# adc.net
KiCad netlist of a schematic drawn in EAGLE
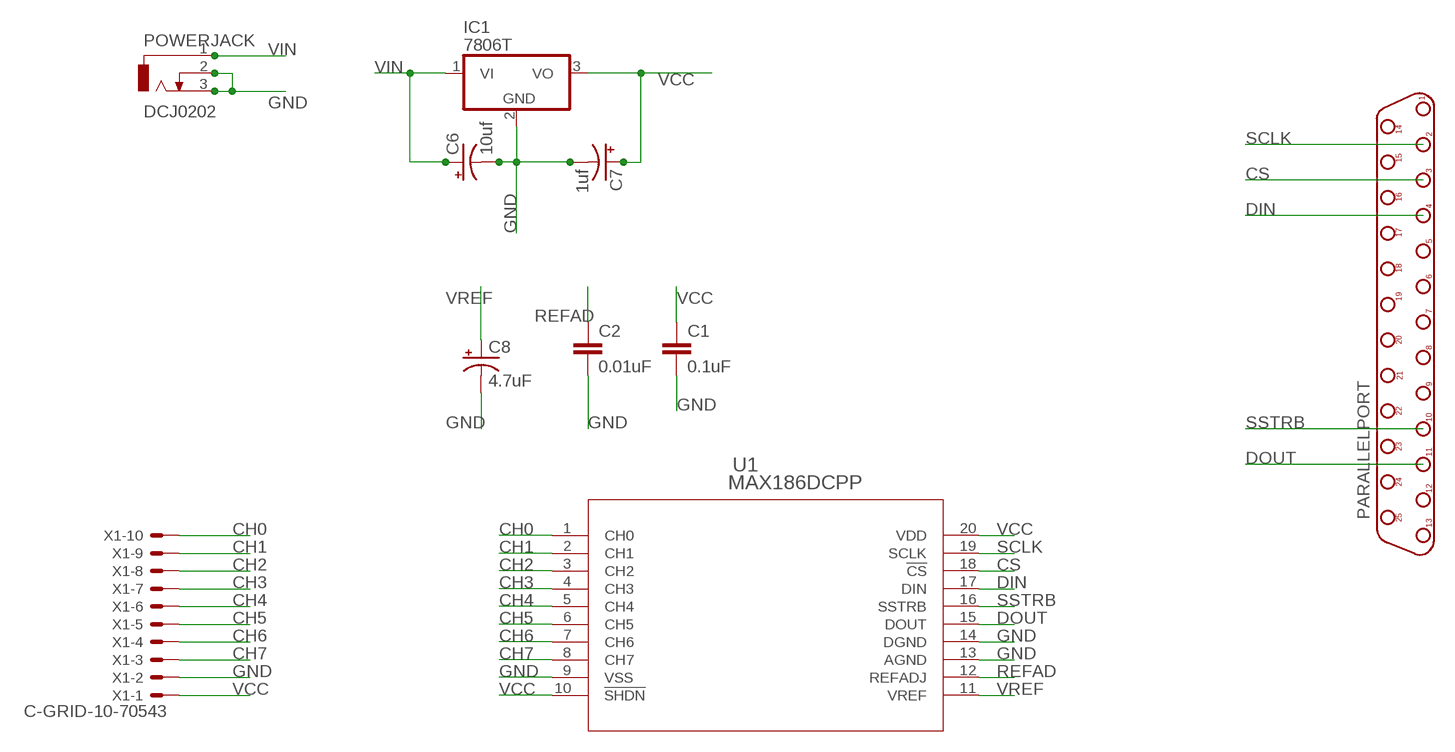
[diagram p0: schematic, sheet 1]

(export (version "E")
  (design (tool "Eeschema 10.0.6"))
  (components
    (comp (ref "C1")
      (value "0.1uF")
      (footprint "eagle-import:C050-035X075")
      (libsource (lib "eagle-import") (part "C-EU050-035X075"))
    )
    (comp (ref "C2")
      (value "0.01uF")
      (footprint "eagle-import:C050-035X075")
      (fields (field (name "MPN") "B32529C1103J189"))
      (libsource (lib "eagle-import") (part "C-EU050-035X075"))
    )
    (comp (ref "C6")
      (value "10uf")
      (footprint "eagle-import:E2-5")
      (libsource (lib "eagle-import") (part "CPOL-USE2-5"))
    )
    (comp (ref "C7")
      (value "1uf")
      (footprint "eagle-import:E2-5")
      (libsource (lib "eagle-import") (part "CPOL-USE2-5"))
    )
    (comp (ref "C8")
      (value "4.7uF")
      (footprint "eagle-import:E2-5")
      (libsource (lib "eagle-import") (part "CPOL-USE2-5"))
    )
    (comp (ref "IC1")
      (value "7806T")
      (footprint "eagle-import:TO220H")
      (libsource (lib "eagle-import") (part "78T06"))
    )
    (comp (ref "PARALLELPORT")
      (value "DB25F")
      (footprint "eagle-import:D-25F")
      (libsource (lib "eagle-import") (part "DB25F"))
    )
    (comp (ref "POWERJACK")
      (value "DCJ0202")
      (footprint "eagle-import:DCJ0202")
      (libsource (lib "eagle-import") (part "DCJ0202"))
    )
    (comp (ref "U1")
      (value "MAX186DCPP")
      (footprint "eagle-import:21-0043D_20")
      (libsource (lib "eagle-import") (part "MAX186DCPP"))
    )
    (comp (ref "X1")
      (value "C-GRID-10-70543")
      (footprint "eagle-import:70543-10")
      (libsource (lib "eagle-import") (part "C-GRID-10-70543"))
    )
  )
  (nets
    (net (code "1") (name "/CH0") (class "Default")
      (node (ref "U1") (pin "1") (pinfunction "CH0_1") (pintype "bidirectional"))
      (node (ref "X1") (pin "10") (pinfunction "S_10") (pintype "passive"))
    )
    (net (code "2") (name "/CH1") (class "Default")
      (node (ref "U1") (pin "2") (pinfunction "CH1_2") (pintype "bidirectional"))
      (node (ref "X1") (pin "9") (pinfunction "S_9") (pintype "passive"))
    )
    (net (code "3") (name "/CH2") (class "Default")
      (node (ref "U1") (pin "3") (pinfunction "CH2_3") (pintype "bidirectional"))
      (node (ref "X1") (pin "8") (pinfunction "S_8") (pintype "passive"))
    )
    (net (code "4") (name "/CH3") (class "Default")
      (node (ref "U1") (pin "4") (pinfunction "CH3_4") (pintype "bidirectional"))
      (node (ref "X1") (pin "7") (pinfunction "S_7") (pintype "passive"))
    )
    (net (code "5") (name "/CH4") (class "Default")
      (node (ref "U1") (pin "5") (pinfunction "CH4_5") (pintype "bidirectional"))
      (node (ref "X1") (pin "6") (pinfunction "S_6") (pintype "passive"))
    )
    (net (code "6") (name "/CH5") (class "Default")
      (node (ref "U1") (pin "6") (pinfunction "CH5_6") (pintype "bidirectional"))
      (node (ref "X1") (pin "5") (pinfunction "S_5") (pintype "passive"))
    )
    (net (code "7") (name "/CH6") (class "Default")
      (node (ref "U1") (pin "7") (pinfunction "CH6_7") (pintype "bidirectional"))
      (node (ref "X1") (pin "4") (pinfunction "S_4") (pintype "passive"))
    )
    (net (code "8") (name "/CH7") (class "Default")
      (node (ref "U1") (pin "8") (pinfunction "CH7_8") (pintype "bidirectional"))
      (node (ref "X1") (pin "3") (pinfunction "S_3") (pintype "passive"))
    )
    (net (code "9") (name "/CS") (class "Default")
      (node (ref "PARALLELPORT") (pin "3") (pinfunction "3_3") (pintype "passive"))
      (node (ref "U1") (pin "18") (pinfunction "~{CS}_18") (pintype "bidirectional"))
    )
    (net (code "10") (name "/DIN") (class "Default")
      (node (ref "PARALLELPORT") (pin "4") (pinfunction "4_4") (pintype "passive"))
      (node (ref "U1") (pin "17") (pinfunction "DIN_17") (pintype "input"))
    )
    (net (code "11") (name "/DOUT") (class "Default")
      (node (ref "PARALLELPORT") (pin "11") (pinfunction "11_11") (pintype "passive"))
      (node (ref "U1") (pin "15") (pinfunction "DOUT_15") (pintype "output"))
    )
    (net (code "12") (name "/GND") (class "Default")
      (node (ref "C1") (pin "2") (pinfunction "2_2") (pintype "passive"))
      (node (ref "C2") (pin "2") (pinfunction "2_2") (pintype "passive"))
      (node (ref "C6") (pin "-") (pinfunction "-_-") (pintype "passive"))
      (node (ref "C7") (pin "-") (pinfunction "-_-") (pintype "passive"))
      (node (ref "C8") (pin "-") (pinfunction "-_-") (pintype "passive"))
      (node (ref "IC1") (pin "2") (pinfunction "GND_2") (pintype "passive"))
      (node (ref "POWERJACK") (pin "2") (pinfunction "2_2") (pintype "passive"))
      (node (ref "POWERJACK") (pin "3") (pinfunction "3_3") (pintype "passive"))
      (node (ref "U1") (pin "13") (pinfunction "AGND_13") (pintype "power_in"))
      (node (ref "U1") (pin "14") (pinfunction "DGND_14") (pintype "power_in"))
      (node (ref "U1") (pin "9") (pinfunction "VSS_9") (pintype "power_in"))
      (node (ref "X1") (pin "2") (pinfunction "S_2") (pintype "passive"))
    )
    (net (code "13") (name "/REFAD") (class "Default")
      (node (ref "C2") (pin "1") (pinfunction "1_1") (pintype "passive"))
      (node (ref "U1") (pin "12") (pinfunction "REFADJ_12") (pintype "bidirectional"))
    )
    (net (code "14") (name "/SCLK") (class "Default")
      (node (ref "PARALLELPORT") (pin "2") (pinfunction "2_2") (pintype "passive"))
      (node (ref "U1") (pin "19") (pinfunction "SCLK_19") (pintype "bidirectional"))
    )
    (net (code "15") (name "/SSTRB") (class "Default")
      (node (ref "PARALLELPORT") (pin "10") (pinfunction "10_10") (pintype "passive"))
      (node (ref "U1") (pin "16") (pinfunction "SSTRB_16") (pintype "bidirectional"))
    )
    (net (code "16") (name "/VCC") (class "Default")
      (node (ref "C1") (pin "1") (pinfunction "1_1") (pintype "passive"))
      (node (ref "C7") (pin "+") (pinfunction "+_+") (pintype "passive"))
      (node (ref "IC1") (pin "3") (pinfunction "VO_3") (pintype "passive"))
      (node (ref "U1") (pin "10") (pinfunction "~{SHDN}_10") (pintype "bidirectional"))
      (node (ref "U1") (pin "20") (pinfunction "VDD_20") (pintype "power_in"))
      (node (ref "X1") (pin "1") (pinfunction "S_1") (pintype "passive"))
    )
    (net (code "17") (name "/VIN") (class "Default")
      (node (ref "C6") (pin "+") (pinfunction "+_+") (pintype "passive"))
      (node (ref "IC1") (pin "1") (pinfunction "VI_1") (pintype "input"))
      (node (ref "POWERJACK") (pin "1") (pinfunction "1_1") (pintype "passive"))
    )
    (net (code "18") (name "/VREF") (class "Default")
      (node (ref "C8") (pin "+") (pinfunction "+_+") (pintype "passive"))
      (node (ref "U1") (pin "11") (pinfunction "VREF_11") (pintype "power_in"))
    )
    (net (code "19") (name "unconnected-(PARALLELPORT-Pad1)") (class "Default")
      (node (ref "PARALLELPORT") (pin "1") (pinfunction "1_1") (pintype "passive"))
    )
    (net (code "20") (name "unconnected-(PARALLELPORT-Pad5)") (class "Default")
      (node (ref "PARALLELPORT") (pin "5") (pinfunction "5_5") (pintype "passive"))
    )
    (net (code "21") (name "unconnected-(PARALLELPORT-Pad6)") (class "Default")
      (node (ref "PARALLELPORT") (pin "6") (pinfunction "6_6") (pintype "passive"))
    )
    (net (code "22") (name "unconnected-(PARALLELPORT-Pad7)") (class "Default")
      (node (ref "PARALLELPORT") (pin "7") (pinfunction "7_7") (pintype "passive"))
    )
    (net (code "23") (name "unconnected-(PARALLELPORT-Pad8)") (class "Default")
      (node (ref "PARALLELPORT") (pin "8") (pinfunction "8_8") (pintype "passive"))
    )
    (net (code "24") (name "unconnected-(PARALLELPORT-Pad9)") (class "Default")
      (node (ref "PARALLELPORT") (pin "9") (pinfunction "9_9") (pintype "passive"))
    )
    (net (code "25") (name "unconnected-(PARALLELPORT-Pad12)") (class "Default")
      (node (ref "PARALLELPORT") (pin "12") (pinfunction "12_12") (pintype "passive"))
    )
    (net (code "26") (name "unconnected-(PARALLELPORT-Pad13)") (class "Default")
      (node (ref "PARALLELPORT") (pin "13") (pinfunction "13_13") (pintype "passive"))
    )
    (net (code "27") (name "unconnected-(PARALLELPORT-Pad14)") (class "Default")
      (node (ref "PARALLELPORT") (pin "14") (pinfunction "14_14") (pintype "passive"))
    )
    (net (code "28") (name "unconnected-(PARALLELPORT-Pad15)") (class "Default")
      (node (ref "PARALLELPORT") (pin "15") (pinfunction "15_15") (pintype "passive"))
    )
    (net (code "29") (name "unconnected-(PARALLELPORT-Pad16)") (class "Default")
      (node (ref "PARALLELPORT") (pin "16") (pinfunction "16_16") (pintype "passive"))
    )
    (net (code "30") (name "unconnected-(PARALLELPORT-Pad17)") (class "Default")
      (node (ref "PARALLELPORT") (pin "17") (pinfunction "17_17") (pintype "passive"))
    )
    (net (code "31") (name "unconnected-(PARALLELPORT-Pad18)") (class "Default")
      (node (ref "PARALLELPORT") (pin "18") (pinfunction "18_18") (pintype "passive"))
    )
    (net (code "32") (name "unconnected-(PARALLELPORT-Pad19)") (class "Default")
      (node (ref "PARALLELPORT") (pin "19") (pinfunction "19_19") (pintype "passive"))
    )
    (net (code "33") (name "unconnected-(PARALLELPORT-Pad20)") (class "Default")
      (node (ref "PARALLELPORT") (pin "20") (pinfunction "20_20") (pintype "passive"))
    )
    (net (code "34") (name "unconnected-(PARALLELPORT-Pad21)") (class "Default")
      (node (ref "PARALLELPORT") (pin "21") (pinfunction "21_21") (pintype "passive"))
    )
    (net (code "35") (name "unconnected-(PARALLELPORT-Pad22)") (class "Default")
      (node (ref "PARALLELPORT") (pin "22") (pinfunction "22_22") (pintype "passive"))
    )
    (net (code "36") (name "unconnected-(PARALLELPORT-Pad23)") (class "Default")
      (node (ref "PARALLELPORT") (pin "23") (pinfunction "23_23") (pintype "passive"))
    )
    (net (code "37") (name "unconnected-(PARALLELPORT-Pad24)") (class "Default")
      (node (ref "PARALLELPORT") (pin "24") (pinfunction "24_24") (pintype "passive"))
    )
    (net (code "38") (name "unconnected-(PARALLELPORT-Pad25)") (class "Default")
      (node (ref "PARALLELPORT") (pin "25") (pinfunction "25_25") (pintype "passive"))
    )
  )
)
